# SH3_-_5V_BUCK_CONVERTER.net
KiCad netlist of a schematic drawn in Altium Designer
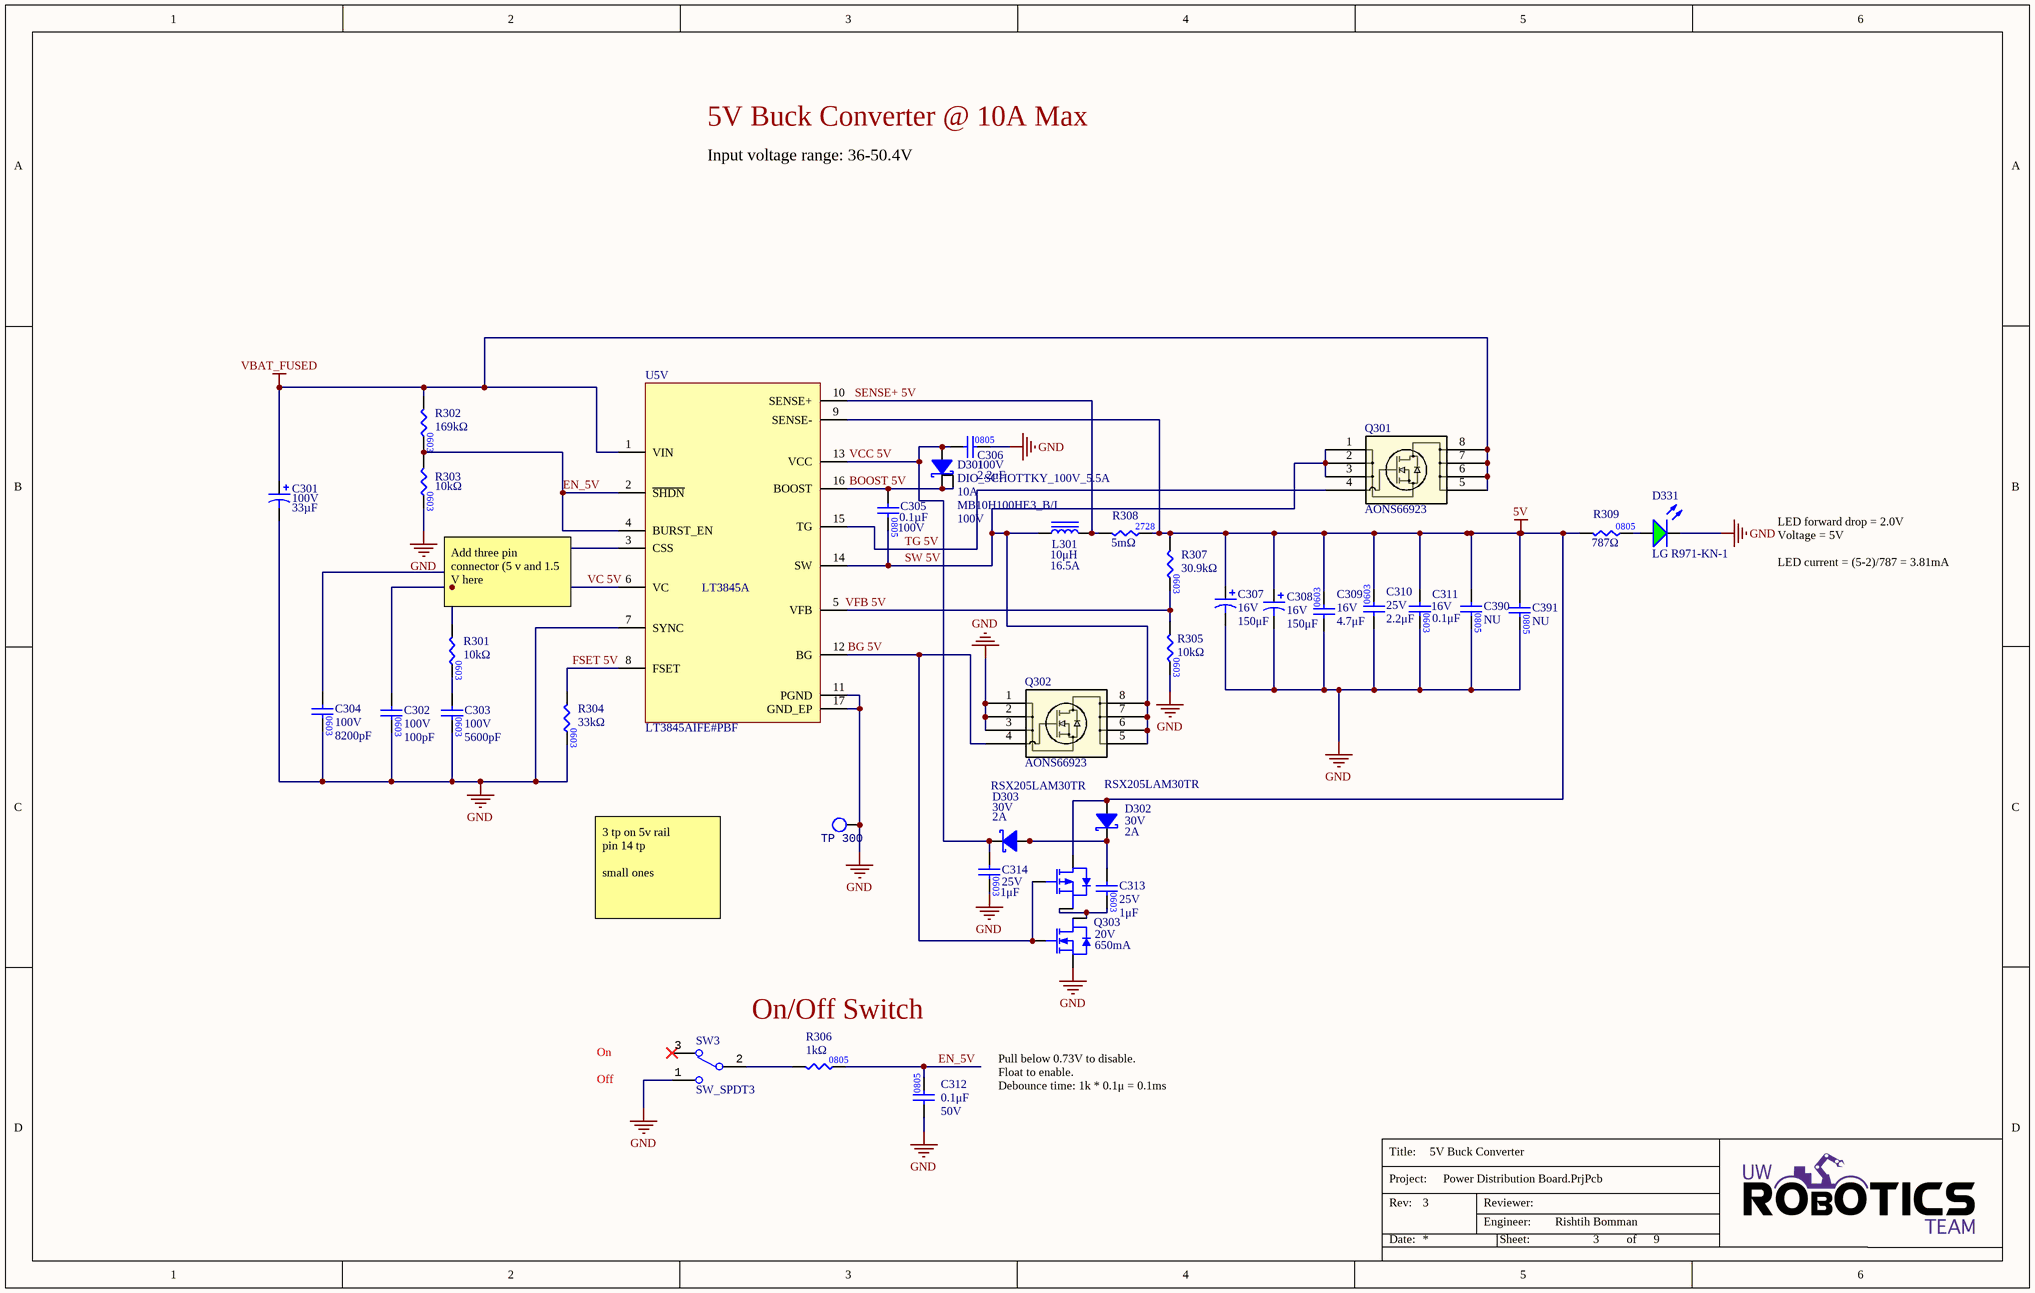
[diagram p0: SH3 - 5V BUCK CONVERTER.SchDoc]

(export (version "E")
  (design (tool "Eeschema 10.0.6"))
  (components
    (comp (ref "C301")
      (value "33µF")
      (footprint "CAP_J-V_8X10P5_RUB-M")
      (description "CAP. ALUM 33UF 100V 20% SMD")
      (fields (field (name "VOLTAGE RATING") "100V") (field (name "Comment") "CAP_33uF_100V_ALUM"))
      (libsource (lib "UWRT_Schematic_Library_2020") (part "CAP_33uF_100V_ALUM"))
    )
    (comp (ref "C302")
      (value "100pF")
      (footprint "CAP0603")
      (description "CAP CER 100PF 100V C0G/NP0 0603")
      (fields (field (name "VOLTAGE RATING") "100V") (field (name "Comment") "CAP_100pF_100V_0603"))
      (libsource (lib "UWRT_Schematic_Library_2020") (part "CAP_100pF_100V_0603"))
    )
    (comp (ref "C303")
      (value "5600pF")
      (footprint "CAP0603")
      (description "CAP CER 5600PF 100V X7R 0603")
      (fields (field (name "VOLTAGE RATING") "100V") (field (name "Comment") "CAP_5600pF_100V_0603"))
      (libsource (lib "UWRT_Schematic_Library_2020") (part "CAP_5600pF_100V_0603"))
    )
    (comp (ref "C304")
      (value "8200pF")
      (footprint "CAP0603")
      (description "CAP CER 8200PF 100V X7R 0603")
      (fields (field (name "VOLTAGE RATING") "100V") (field (name "Comment") "CAP_8200pF_100V_0603"))
      (libsource (lib "UWRT_Schematic_Library_2020") (part "CAP_8200pF_100V_0603"))
    )
    (comp (ref "C305")
      (value "0.1µF")
      (footprint "CAP0805")
      (description "CAP CER 0.1UF 100V X7R 0805")
      (fields (field (name "VOLTAGE RATING") "100V") (field (name "Comment") "CAP_0.1uF_100V_0805"))
      (libsource (lib "UWRT_Schematic_Library_2020") (part "CAP_0.1uF_100V_0805"))
    )
    (comp (ref "C306")
      (value "2.2μF")
      (footprint "CAP2012")
      (description "CAP CER 2.2UF 100V X7T 0805")
      (fields
        (field (name "LCSC PART #") "C5378")
        (field (name "VOLTAGE RATING") "100V")
        (field (name "Comment") "CAP_2.2uF_100V_0805")
      )
      (libsource (lib "UWRT_Schematic_Library_2020") (part "CAP_2.2uF_100V_0805"))
    )
    (comp (ref "C307")
      (value "150μF")
      (footprint "CAP2917")
      (description "CAP TANT 150UF 10% 16V 2917")
      (fields (field (name "VOLTAGE RATING") "16V") (field (name "Comment") "CAP_150uF_16V_TANT_1"))
      (libsource (lib "UWRT_Schematic_Library_2020") (part "CAP_150uF_16V_TANT_1"))
    )
    (comp (ref "C308")
      (value "150μF")
      (footprint "CAP2917")
      (description "CAP TANT 150UF 10% 16V 2917")
      (fields (field (name "VOLTAGE RATING") "16V") (field (name "Comment") "CAP_150uF_16V_TANT_1"))
      (libsource (lib "UWRT_Schematic_Library_2020") (part "CAP_150uF_16V_TANT_1"))
    )
    (comp (ref "C309")
      (value "4.7μF")
      (footprint "CAP0603")
      (description "CAP CER 4.7UF 16V X6S 0603")
      (fields (field (name "VOLTAGE RATING") "16V") (field (name "Comment") "CAP_4.7uF_16V_0603"))
      (libsource (lib "UWRT_Schematic_Library_2020") (part "CAP_4.7uF_16V_0603"))
    )
    (comp (ref "C310")
      (value "2.2μF")
      (footprint "CAP0603")
      (description "CAP CER 2.2UF 25V X5R 0603")
      (fields (field (name "VOLTAGE RATING") "25V") (field (name "Comment") "CAP_2.2uF_25V_0603"))
      (libsource (lib "UWRT_Schematic_Library_2020") (part "CAP_2.2uF_25V_0603"))
    )
    (comp (ref "C311")
      (value "0.1μF")
      (footprint "CAP0603")
      (description "CAP CER 0.1UF 16V X7R 0603")
      (fields (field (name "VOLTAGE RATING") "16V") (field (name "Comment") "CAP_0.1uF_16V_0603"))
      (libsource (lib "UWRT_Schematic_Library_2020") (part "CAP_0.1uF_16V_0603"))
    )
    (comp (ref "C312")
      (value "0.1μF")
      (footprint "CAP2012")
      (description "CAP CER 0.1UF 50V X7R 0805")
      (fields
        (field (name "VOLTAGE RATING") "50V")
        (field (name "LCSC PART #") "C49678")
        (field (name "Comment") "CAP_0.1uF_50V_0805")
      )
      (libsource (lib "UWRT_Schematic_Library_2020") (part "CAP_0.1uF_50V_0805"))
    )
    (comp (ref "C313")
      (value "1μF")
      (footprint "CAP0603")
      (description "CAP CER 1UF 25V X5R 0603")
      (fields (field (name "VOLTAGE RATING") "25V") (field (name "Comment") "CAP_1uF_25V_0603"))
      (libsource (lib "UWRT_Schematic_Library_2020") (part "CAP_1uF_25V_0603"))
    )
    (comp (ref "C314")
      (value "1μF")
      (footprint "CAP0603")
      (description "CAP CER 1UF 25V X5R 0603")
      (fields (field (name "VOLTAGE RATING") "25V") (field (name "Comment") "CAP_1uF_25V_0603"))
      (libsource (lib "UWRT_Schematic_Library_2020") (part "CAP_1uF_25V_0603"))
    )
    (comp (ref "C390")
      (value "NU")
      (footprint "CAP0805")
      (description "PLACEHOLDER CAPACITOR")
      (fields (field (name "Comment") "CAP_NU_0805"))
      (libsource (lib "UWRT_Schematic_Library_2020") (part "CAP_NU_0805"))
    )
    (comp (ref "C391")
      (value "NU")
      (footprint "CAP0805")
      (description "PLACEHOLDER CAPACITOR")
      (fields (field (name "Comment") "CAP_NU_0805"))
      (libsource (lib "UWRT_Schematic_Library_2020") (part "CAP_NU_0805"))
    )
    (comp (ref "D301")
      (value "DIO_SCHOTTKY_100V_5.5A")
      (footprint "D2PAK (TO-263AB)")
      (description "DIODE SCHOTTKY 100V 10A TO263AB")
      (fields
        (field (name "FORWARD CURRENT") "10A")
        (field (name "MANUFACTURER PART NUMBER 1") "MB10H100HE3_B/I")
        (field (name "VR (MAX)") "100V")
      )
      (libsource (lib "UWRT_Schematic_Library_2020") (part "DIO_SCHOTTKY_100V_10A"))
    )
    (comp (ref "D302")
      (value "DIO_SCHOTTKY_30V_2A")
      (footprint "SOD-128")
      (description "DIODE SCHOTTKY 30V 2A PMDTM")
      (fields
        (field (name "MANUFACTURER PART NUMBER 1") "RSX205LAM30TR")
        (field (name "VR (MAX)") "30V")
        (field (name "IO") "2A")
      )
      (libsource (lib "UWRT_Schematic_Library_2020") (part "DIO_SCHOTTKY_30V_2A"))
    )
    (comp (ref "D303")
      (value "DIO_SCHOTTKY_30V_2A")
      (footprint "SOD-128")
      (description "DIODE SCHOTTKY 30V 2A PMDTM")
      (fields
        (field (name "MANUFACTURER PART NUMBER 1") "RSX205LAM30TR")
        (field (name "VR (MAX)") "30V")
        (field (name "IO") "2A")
      )
      (libsource (lib "UWRT_Schematic_Library_2020") (part "DIO_SCHOTTKY_30V_2A"))
    )
    (comp (ref "D331")
      (value "LED_GREEN")
      (footprint "LED_0805_GREEN")
      (description "LED GREEN DIFFUSED 0805 SMD")
      (fields (field (name "MANUFACTURER PART NUMBER 1") "LG R971-KN-1"))
      (libsource (lib "UWRT_Schematic_Library_2020") (part "LED_GREEN"))
    )
    (comp (ref "L301")
      (value "IND_10uH_16.5A")
      (footprint "IND_MWLA1707S")
      (description "FIXED IND 10UH 13MOHM 24000MA")
      (fields (field (name "CURRENT RATING") "16.5A") (field (name "INDUCTANCE") "10μH"))
      (libsource (lib "UWRT_Schematic_Library_2020") (part "IND_10uH_16.5A"))
    )
    (comp (ref "Q301")
      (value "AONS66923")
      (footprint "DFN5X6_8L_EP1_P_AOS-L")
      (description "MOSFET N-CH 100V 15A/47A 8DFN")
      (fields (field (name "COPYRIGHT") "Copyright (C) 2022 Ultra Librarian. All rights reserved."))
      (libsource (lib "UWRT_Schematic_Library_2020") (part "NMOS_100V_15/47A_1"))
    )
    (comp (ref "Q302")
      (value "AONS66923")
      (footprint "DFN5X6_8L_EP1_P_AOS-L")
      (description "MOSFET N-CH 100V 15A/47A 8DFN")
      (fields (field (name "COPYRIGHT") "Copyright (C) 2022 Ultra Librarian. All rights reserved."))
      (libsource (lib "UWRT_Schematic_Library_2020") (part "NMOS_100V_15/47A_1"))
    )
    (comp (ref "Q303")
      (value "DUAL_MOSFET_20V_650mA_P&N")
      (footprint "ES6-M")
      (description "MOSFET N/P-CH 20V 0.65A SOT563")
      (fields
        (field (name "CONTINUOUS DRAIN CURRENT (ID)") "650mA")
        (field (name "DRAIN TO SOURCE VOLTAGE (VDSS)") "20V")
      )
      (libsource (lib "UWRT_Schematic_Library_2020") (part "DUAL_MOSFET_20V_650mA_P&N"))
    )
    (comp (ref "R301")
      (value "10kΩ")
      (footprint "RES0603")
      (description "RES 10K OHM 5% 1/10W 0603")
      (fields (field (name "Comment") "RES_10kΩ_0603_5%"))
      (libsource (lib "UWRT_Schematic_Library_2020") (part "RES_10kΩ_0603_5%"))
    )
    (comp (ref "R302")
      (value "169kΩ")
      (footprint "RES0603")
      (description "RES 169K OHM 1% 1/10W 0603")
      (fields (field (name "Comment") "RES_169kΩ_0603_1%"))
      (libsource (lib "UWRT_Schematic_Library_2020") (part "RES_169kΩ_0603_1%"))
    )
    (comp (ref "R303")
      (value "10kΩ")
      (footprint "RES0603")
      (description "RES 10K OHM 5% 1/10W 0603")
      (fields (field (name "Comment") "RES_10kΩ_0603_5%"))
      (libsource (lib "UWRT_Schematic_Library_2020") (part "RES_10kΩ_0603_5%"))
    )
    (comp (ref "R304")
      (value "33kΩ")
      (footprint "RES0603")
      (description "RES 33K OHM 5% 1/10W 0603")
      (fields (field (name "Comment") "RES_33kΩ_0603_5%"))
      (libsource (lib "UWRT_Schematic_Library_2020") (part "RES_33kΩ_0603_5%"))
    )
    (comp (ref "R305")
      (value "10kΩ")
      (footprint "RES0603")
      (description "RES 10K OHM 5% 1/10W 0603")
      (fields (field (name "Comment") "RES_10kΩ_0603_5%"))
      (libsource (lib "UWRT_Schematic_Library_2020") (part "RES_10kΩ_0603_5%"))
    )
    (comp (ref "R306")
      (value "1kΩ")
      (footprint "RES0805")
      (description "RES 1K OHM 1% 1/8W 0805")
      (fields (field (name "LCSC PART #") "C17513") (field (name "Comment") "RES_1kΩ_0805_1%_1"))
      (libsource (lib "UWRT_Schematic_Library_2020") (part "RES_1kΩ_0805_1%_1"))
    )
    (comp (ref "R307")
      (value "30.9kΩ")
      (footprint "RES0603")
      (description "RES 30.9K OHM 0.5% 1/10W 0603")
      (fields (field (name "TOLERANCE") "0.5%") (field (name "Comment") "RES_30.9kΩ_0603_0.5%"))
      (libsource (lib "UWRT_Schematic_Library_2020") (part "RES_30.9kΩ_0603_0.5%"))
    )
    (comp (ref "R308")
      (value "5mΩ")
      (footprint "STA_CSSH2728_STP-M")
      (description "RES 0.005 OHM 1% 4W 2827")
      (fields (field (name "Comment") "RES_5mΩ_2728_1%"))
      (libsource (lib "UWRT_Schematic_Library_2020") (part "RES_5mΩ_2728_1%"))
    )
    (comp (ref "R309")
      (value "787Ω")
      (footprint "RES0805")
      (description "RES 787 OHM 1% 1/8W 0805")
      (fields (field (name "Comment") "RES_787Ω_0805_1%"))
      (libsource (lib "UWRT_Schematic_Library_2020") (part "RES_787Ω_0805_1%"))
    )
    (comp (ref "SW3")
      (value "SW_SPDT3")
      (footprint "100SP1T1B4M2QE")
      (description "SWITCH TOGGLE SPDT 5A 120V")
      (libsource (lib "UWRT_Schematic_Library_2020") (part "SW_SPDT"))
    )
    (comp (ref "TP 300")
      (value "TESTPOINT_LOOP")
      (footprint "TESTPOINT_LOOP")
      (description "TESTPOINT THRUHOLE")
      (libsource (lib "UWRT_Schematic_Library_2020") (part "TESTPOINT_LOOP"))
    )
    (comp (ref "U5V")
      (value "BUCK_LT3845A")
      (footprint "LT3845AIFE#PBF")
      (description "IC REG CTRLR BUCK 16TSSOP")
      (fields (field (name "MANUFACTURER PART NUMBER 1") "LT3845AIFE#PBF"))
      (libsource (lib "UWRT_Schematic_Library_2020") (part "BUCK_LT3845A"))
    )
  )
  (nets
    (net (code "1") (name "/BG 5V") (class "Default")
      (node (ref "Q302") (pin "4") (pinfunction "4_4") (pintype "passive"))
      (node (ref "Q303") (pin "2") (pinfunction "GATE-N_2") (pintype "passive"))
      (node (ref "Q303") (pin "5") (pinfunction "GATE-P_5") (pintype "passive"))
      (node (ref "U5V") (pin "12") (pinfunction "BG_12") (pintype "passive"))
    )
    (net (code "2") (name "/BOOST 5V") (class "Default")
      (node (ref "C305") (pin "1") (pinfunction "1_1") (pintype "passive"))
      (node (ref "D301") (pin "1") (pinfunction "Cathode_1") (pintype "passive"))
      (node (ref "D301") (pin "3") (pinfunction "Heatsink_(K)_3") (pintype "passive"))
      (node (ref "U5V") (pin "16") (pinfunction "BOOST_16") (pintype "passive"))
    )
    (net (code "3") (name "/EN_5V") (class "Default")
      (node (ref "C312") (pin "2") (pinfunction "2_2") (pintype "passive"))
      (node (ref "R302") (pin "2") (pinfunction "2_2") (pintype "passive"))
      (node (ref "R303") (pin "1") (pinfunction "1_1") (pintype "passive"))
      (node (ref "R306") (pin "2") (pinfunction "2_2") (pintype "passive"))
      (node (ref "U5V") (pin "2") (pinfunction "~{SHDN}_2") (pintype "passive"))
      (node (ref "U5V") (pin "4") (pinfunction "BURST_EN_4") (pintype "passive"))
    )
    (net (code "4") (name "/FSET 5V") (class "Default")
      (node (ref "R304") (pin "1") (pinfunction "1_1") (pintype "passive"))
      (node (ref "U5V") (pin "8") (pinfunction "FSET_8") (pintype "passive"))
    )
    (net (code "5") (name "/SENSE+ 5V") (class "Default")
      (node (ref "L301") (pin "2") (pinfunction "2_2") (pintype "passive"))
      (node (ref "R308") (pin "1") (pinfunction "1_1") (pintype "passive"))
      (node (ref "U5V") (pin "10") (pinfunction "SENSE+_10") (pintype "passive"))
    )
    (net (code "6") (name "/SW 5V") (class "Default")
      (node (ref "C305") (pin "2") (pinfunction "2_2") (pintype "passive"))
      (node (ref "L301") (pin "1") (pinfunction "1_1") (pintype "passive"))
      (node (ref "Q301") (pin "1") (pinfunction "1_1") (pintype "passive"))
      (node (ref "Q301") (pin "2") (pinfunction "2_2") (pintype "passive"))
      (node (ref "Q301") (pin "3") (pinfunction "3_3") (pintype "passive"))
      (node (ref "Q302") (pin "5") (pinfunction "5_5") (pintype "passive"))
      (node (ref "Q302") (pin "6") (pinfunction "6_6") (pintype "passive"))
      (node (ref "Q302") (pin "7") (pinfunction "7_7") (pintype "passive"))
      (node (ref "Q302") (pin "8") (pinfunction "8_8") (pintype "passive"))
      (node (ref "U5V") (pin "14") (pinfunction "SW_14") (pintype "passive"))
    )
    (net (code "7") (name "/TG 5V") (class "Default")
      (node (ref "Q301") (pin "4") (pinfunction "4_4") (pintype "passive"))
      (node (ref "U5V") (pin "15") (pinfunction "TG_15") (pintype "passive"))
    )
    (net (code "8") (name "/VC 5V") (class "Default")
      (node (ref "C302") (pin "1") (pinfunction "1_1") (pintype "passive"))
      (node (ref "R301") (pin "1") (pinfunction "1_1") (pintype "passive"))
      (node (ref "U5V") (pin "6") (pinfunction "VC_6") (pintype "passive"))
    )
    (net (code "9") (name "/VCC 5V") (class "Default")
      (node (ref "C306") (pin "1") (pinfunction "1_1") (pintype "passive"))
      (node (ref "C314") (pin "1") (pinfunction "1_1") (pintype "passive"))
      (node (ref "D301") (pin "2") (pinfunction "Anode_2") (pintype "passive"))
      (node (ref "D303") (pin "2") (pinfunction "Cathode_2") (pintype "passive"))
      (node (ref "U5V") (pin "13") (pinfunction "VCC_13") (pintype "passive"))
    )
    (net (code "11") (name "5V") (class "Default")
      (node (ref "C307") (pin "1") (pinfunction "1_1") (pintype "passive"))
      (node (ref "C308") (pin "1") (pinfunction "1_1") (pintype "passive"))
      (node (ref "C309") (pin "2") (pinfunction "2_2") (pintype "passive"))
      (node (ref "C310") (pin "2") (pinfunction "2_2") (pintype "passive"))
      (node (ref "C311") (pin "1") (pinfunction "1_1") (pintype "passive"))
      (node (ref "C390") (pin "1") (pinfunction "1_1") (pintype "passive"))
      (node (ref "C391") (pin "1") (pinfunction "1_1") (pintype "passive"))
      (node (ref "D302") (pin "1") (pinfunction "Anode_1") (pintype "passive"))
      (node (ref "Q303") (pin "4") (pinfunction "DRAIN-P_4") (pintype "passive"))
      (node (ref "R307") (pin "1") (pinfunction "1_1") (pintype "passive"))
      (node (ref "R308") (pin "2") (pinfunction "2_2") (pintype "passive"))
      (node (ref "R309") (pin "1") (pinfunction "1_1") (pintype "passive"))
      (node (ref "U5V") (pin "9") (pinfunction "SENSE-_9") (pintype "passive"))
    )
    (net (code "12") (name "GND") (class "Default")
      (node (ref "C301") (pin "2") (pinfunction "2_2") (pintype "passive"))
      (node (ref "C302") (pin "2") (pinfunction "2_2") (pintype "passive"))
      (node (ref "C303") (pin "2") (pinfunction "2_2") (pintype "passive"))
      (node (ref "C304") (pin "2") (pinfunction "2_2") (pintype "passive"))
      (node (ref "C306") (pin "2") (pinfunction "2_2") (pintype "passive"))
      (node (ref "C307") (pin "2") (pinfunction "2_2") (pintype "passive"))
      (node (ref "C308") (pin "2") (pinfunction "2_2") (pintype "passive"))
      (node (ref "C309") (pin "1") (pinfunction "1_1") (pintype "passive"))
      (node (ref "C310") (pin "1") (pinfunction "1_1") (pintype "passive"))
      (node (ref "C311") (pin "2") (pinfunction "2_2") (pintype "passive"))
      (node (ref "C312") (pin "1") (pinfunction "1_1") (pintype "passive"))
      (node (ref "C314") (pin "2") (pinfunction "2_2") (pintype "passive"))
      (node (ref "C390") (pin "2") (pinfunction "2_2") (pintype "passive"))
      (node (ref "C391") (pin "2") (pinfunction "2_2") (pintype "passive"))
      (node (ref "D331") (pin "2") (pinfunction "K_2") (pintype "passive"))
      (node (ref "Q302") (pin "1") (pinfunction "1_1") (pintype "passive"))
      (node (ref "Q302") (pin "2") (pinfunction "2_2") (pintype "passive"))
      (node (ref "Q302") (pin "3") (pinfunction "3_3") (pintype "passive"))
      (node (ref "Q303") (pin "1") (pinfunction "SOURCE-N_1") (pintype "passive"))
      (node (ref "R303") (pin "2") (pinfunction "2_2") (pintype "passive"))
      (node (ref "R304") (pin "2") (pinfunction "2_2") (pintype "passive"))
      (node (ref "R305") (pin "2") (pinfunction "2_2") (pintype "passive"))
      (node (ref "SW3") (pin "1") (pinfunction "1_1") (pintype "passive"))
      (node (ref "TP 300") (pin "1") (pintype "passive"))
      (node (ref "U5V") (pin "11") (pinfunction "PGND_11") (pintype "power_in"))
      (node (ref "U5V") (pin "17") (pinfunction "GND_EP_17") (pintype "power_in"))
      (node (ref "U5V") (pin "7") (pinfunction "SYNC_7") (pintype "passive"))
    )
    (net (code "13") (name "Net-(C303-Pad1)") (class "Default")
      (node (ref "C303") (pin "1") (pinfunction "1_1") (pintype "passive"))
      (node (ref "R301") (pin "2") (pinfunction "2_2") (pintype "passive"))
    )
    (net (code "14") (name "Net-(C313-Pad2)") (class "Default")
      (node (ref "C313") (pin "2") (pinfunction "2_2") (pintype "passive"))
      (node (ref "Q303") (pin "3") (pinfunction "GATE-N_3") (pintype "passive"))
      (node (ref "Q303") (pin "6") (pinfunction "GATE-N_6") (pintype "passive"))
    )
    (net (code "15") (name "Net-(D302-Cathode)") (class "Default")
      (node (ref "C313") (pin "1") (pinfunction "1_1") (pintype "passive"))
      (node (ref "D302") (pin "2") (pinfunction "Cathode_2") (pintype "passive"))
      (node (ref "D303") (pin "1") (pinfunction "Anode_1") (pintype "passive"))
    )
    (net (code "16") (name "Net-(D331-A)") (class "Default")
      (node (ref "D331") (pin "1") (pinfunction "A_1") (pintype "passive"))
      (node (ref "R309") (pin "2") (pinfunction "2_2") (pintype "passive"))
    )
    (net (code "17") (name "Net-(R306-Pad1)") (class "Default")
      (node (ref "R306") (pin "1") (pinfunction "1_1") (pintype "passive"))
      (node (ref "SW3") (pin "2") (pinfunction "2_2") (pintype "passive"))
    )
    (net (code "18") (name "Net-(U5V-CSS)") (class "Default")
      (node (ref "C304") (pin "1") (pinfunction "1_1") (pintype "passive"))
      (node (ref "U5V") (pin "3") (pinfunction "CSS_3") (pintype "passive"))
    )
    (net (code "19") (name "Net-(U5V-VFB)") (class "Default")
      (node (ref "R305") (pin "1") (pinfunction "1_1") (pintype "passive"))
      (node (ref "R307") (pin "2") (pinfunction "2_2") (pintype "passive"))
      (node (ref "U5V") (pin "5") (pinfunction "VFB_5") (pintype "passive"))
    )
    (net (code "20") (name "VBAT_FUSED") (class "Default")
      (node (ref "C301") (pin "1") (pinfunction "1_1") (pintype "passive"))
      (node (ref "Q301") (pin "5") (pinfunction "5_5") (pintype "passive"))
      (node (ref "Q301") (pin "6") (pinfunction "6_6") (pintype "passive"))
      (node (ref "Q301") (pin "7") (pinfunction "7_7") (pintype "passive"))
      (node (ref "Q301") (pin "8") (pinfunction "8_8") (pintype "passive"))
      (node (ref "R302") (pin "1") (pinfunction "1_1") (pintype "passive"))
      (node (ref "U5V") (pin "1") (pinfunction "VIN_1") (pintype "passive"))
    )
    (net (code "21") (name "unconnected-(SW3-Pad3)") (class "Default")
      (node (ref "SW3") (pin "3") (pinfunction "3_3") (pintype "passive+no_connect"))
    )
  )
)
